# v002.net
KiCad netlist of a schematic drawn in EAGLE
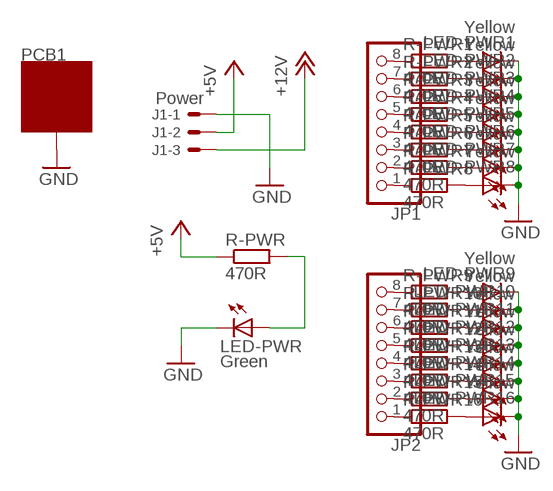
[diagram p0: schematic, sheet 1]

(export (version "E")
  (design (tool "Eeschema 10.0.6"))
  (components
    (comp (ref "J1")
      (value "Power")
      (footprint "eagle-import:6410-03")
      (libsource (lib "eagle-import") (part "22-?-0327-2031"))
    )
    (comp (ref "JP1")
      (value "PINHD-1X8")
      (footprint "eagle-import:1X08")
      (libsource (lib "eagle-import") (part "PINHD-1X8"))
    )
    (comp (ref "JP2")
      (value "PINHD-1X8")
      (footprint "eagle-import:1X08")
      (libsource (lib "eagle-import") (part "PINHD-1X8"))
    )
    (comp (ref "LED-PWR")
      (value "Green")
      (footprint "eagle-import:LED3MM")
      (libsource (lib "eagle-import") (part "LED3MM"))
    )
    (comp (ref "LED-PWR1")
      (value "Yellow")
      (footprint "eagle-import:LED3MM")
      (libsource (lib "eagle-import") (part "LED3MM"))
    )
    (comp (ref "LED-PWR2")
      (value "Yellow")
      (footprint "eagle-import:LED3MM")
      (libsource (lib "eagle-import") (part "LED3MM"))
    )
    (comp (ref "LED-PWR3")
      (value "Yellow")
      (footprint "eagle-import:LED3MM")
      (libsource (lib "eagle-import") (part "LED3MM"))
    )
    (comp (ref "LED-PWR4")
      (value "Yellow")
      (footprint "eagle-import:LED3MM")
      (libsource (lib "eagle-import") (part "LED3MM"))
    )
    (comp (ref "LED-PWR5")
      (value "Yellow")
      (footprint "eagle-import:LED3MM")
      (libsource (lib "eagle-import") (part "LED3MM"))
    )
    (comp (ref "LED-PWR6")
      (value "Yellow")
      (footprint "eagle-import:LED3MM")
      (libsource (lib "eagle-import") (part "LED3MM"))
    )
    (comp (ref "LED-PWR7")
      (value "Yellow")
      (footprint "eagle-import:LED3MM")
      (libsource (lib "eagle-import") (part "LED3MM"))
    )
    (comp (ref "LED-PWR8")
      (value "Yellow")
      (footprint "eagle-import:LED3MM")
      (libsource (lib "eagle-import") (part "LED3MM"))
    )
    (comp (ref "LED-PWR9")
      (value "Yellow")
      (footprint "eagle-import:LED3MM")
      (libsource (lib "eagle-import") (part "LED3MM"))
    )
    (comp (ref "LED-PWR10")
      (value "Yellow")
      (footprint "eagle-import:LED3MM")
      (libsource (lib "eagle-import") (part "LED3MM"))
    )
    (comp (ref "LED-PWR11")
      (value "Yellow")
      (footprint "eagle-import:LED3MM")
      (libsource (lib "eagle-import") (part "LED3MM"))
    )
    (comp (ref "LED-PWR12")
      (value "Yellow")
      (footprint "eagle-import:LED3MM")
      (libsource (lib "eagle-import") (part "LED3MM"))
    )
    (comp (ref "LED-PWR13")
      (value "Yellow")
      (footprint "eagle-import:LED3MM")
      (libsource (lib "eagle-import") (part "LED3MM"))
    )
    (comp (ref "LED-PWR14")
      (value "Yellow")
      (footprint "eagle-import:LED3MM")
      (libsource (lib "eagle-import") (part "LED3MM"))
    )
    (comp (ref "LED-PWR15")
      (value "Yellow")
      (footprint "eagle-import:LED3MM")
      (libsource (lib "eagle-import") (part "LED3MM"))
    )
    (comp (ref "LED-PWR16")
      (value "Yellow")
      (footprint "eagle-import:LED3MM")
      (libsource (lib "eagle-import") (part "LED3MM"))
    )
    (comp (ref "PCB1")
      (value "ZZZ_MODULE05X05")
      (footprint "eagle-import:ZZZ_MODULE_05X05")
      (libsource (lib "eagle-import") (part "ZZZ_MODULE05X05"))
    )
    (comp (ref "R-PWR")
      (value "470R")
      (footprint "eagle-import:0204_7")
      (libsource (lib "eagle-import") (part "R-EU_0204/7"))
    )
    (comp (ref "R-PWR1")
      (value "470R")
      (footprint "eagle-import:0204_7")
      (libsource (lib "eagle-import") (part "R-EU_0204/7"))
    )
    (comp (ref "R-PWR2")
      (value "470R")
      (footprint "eagle-import:0204_7")
      (libsource (lib "eagle-import") (part "R-EU_0204/7"))
    )
    (comp (ref "R-PWR3")
      (value "470R")
      (footprint "eagle-import:0204_7")
      (libsource (lib "eagle-import") (part "R-EU_0204/7"))
    )
    (comp (ref "R-PWR4")
      (value "470R")
      (footprint "eagle-import:0204_7")
      (libsource (lib "eagle-import") (part "R-EU_0204/7"))
    )
    (comp (ref "R-PWR5")
      (value "470R")
      (footprint "eagle-import:0204_7")
      (libsource (lib "eagle-import") (part "R-EU_0204/7"))
    )
    (comp (ref "R-PWR6")
      (value "470R")
      (footprint "eagle-import:0204_7")
      (libsource (lib "eagle-import") (part "R-EU_0204/7"))
    )
    (comp (ref "R-PWR7")
      (value "470R")
      (footprint "eagle-import:0204_7")
      (libsource (lib "eagle-import") (part "R-EU_0204/7"))
    )
    (comp (ref "R-PWR8")
      (value "470R")
      (footprint "eagle-import:0204_7")
      (libsource (lib "eagle-import") (part "R-EU_0204/7"))
    )
    (comp (ref "R-PWR9")
      (value "470R")
      (footprint "eagle-import:0204_7")
      (libsource (lib "eagle-import") (part "R-EU_0204/7"))
    )
    (comp (ref "R-PWR10")
      (value "470R")
      (footprint "eagle-import:0204_7")
      (libsource (lib "eagle-import") (part "R-EU_0204/7"))
    )
    (comp (ref "R-PWR11")
      (value "470R")
      (footprint "eagle-import:0204_7")
      (libsource (lib "eagle-import") (part "R-EU_0204/7"))
    )
    (comp (ref "R-PWR12")
      (value "470R")
      (footprint "eagle-import:0204_7")
      (libsource (lib "eagle-import") (part "R-EU_0204/7"))
    )
    (comp (ref "R-PWR13")
      (value "470R")
      (footprint "eagle-import:0204_7")
      (libsource (lib "eagle-import") (part "R-EU_0204/7"))
    )
    (comp (ref "R-PWR14")
      (value "470R")
      (footprint "eagle-import:0204_7")
      (libsource (lib "eagle-import") (part "R-EU_0204/7"))
    )
    (comp (ref "R-PWR15")
      (value "470R")
      (footprint "eagle-import:0204_7")
      (libsource (lib "eagle-import") (part "R-EU_0204/7"))
    )
    (comp (ref "R-PWR16")
      (value "470R")
      (footprint "eagle-import:0204_7")
      (libsource (lib "eagle-import") (part "R-EU_0204/7"))
    )
  )
  (nets
    (net (code "1") (name "+5V") (class "Default")
      (node (ref "J1") (pin "2") (pinfunction "S_2") (pintype "passive"))
      (node (ref "R-PWR") (pin "1") (pinfunction "1_1") (pintype "passive"))
    )
    (net (code "2") (name "+12V") (class "Default")
      (node (ref "J1") (pin "3") (pinfunction "S_3") (pintype "passive"))
    )
    (net (code "3") (name "GND") (class "Default")
      (node (ref "J1") (pin "1") (pinfunction "S_1") (pintype "passive"))
      (node (ref "LED-PWR") (pin "K") (pinfunction "C_K") (pintype "passive"))
      (node (ref "LED-PWR1") (pin "K") (pinfunction "C_K") (pintype "passive"))
      (node (ref "LED-PWR10") (pin "K") (pinfunction "C_K") (pintype "passive"))
      (node (ref "LED-PWR11") (pin "K") (pinfunction "C_K") (pintype "passive"))
      (node (ref "LED-PWR12") (pin "K") (pinfunction "C_K") (pintype "passive"))
      (node (ref "LED-PWR13") (pin "K") (pinfunction "C_K") (pintype "passive"))
      (node (ref "LED-PWR14") (pin "K") (pinfunction "C_K") (pintype "passive"))
      (node (ref "LED-PWR15") (pin "K") (pinfunction "C_K") (pintype "passive"))
      (node (ref "LED-PWR16") (pin "K") (pinfunction "C_K") (pintype "passive"))
      (node (ref "LED-PWR2") (pin "K") (pinfunction "C_K") (pintype "passive"))
      (node (ref "LED-PWR3") (pin "K") (pinfunction "C_K") (pintype "passive"))
      (node (ref "LED-PWR4") (pin "K") (pinfunction "C_K") (pintype "passive"))
      (node (ref "LED-PWR5") (pin "K") (pinfunction "C_K") (pintype "passive"))
      (node (ref "LED-PWR6") (pin "K") (pinfunction "C_K") (pintype "passive"))
      (node (ref "LED-PWR7") (pin "K") (pinfunction "C_K") (pintype "passive"))
      (node (ref "LED-PWR8") (pin "K") (pinfunction "C_K") (pintype "passive"))
      (node (ref "LED-PWR9") (pin "K") (pinfunction "C_K") (pintype "passive"))
      (node (ref "PCB1") (pin "GND@1") (pinfunction "GND_GND@1") (pintype "power_in"))
      (node (ref "PCB1") (pin "GND@2") (pinfunction "GND_GND@2") (pintype "power_in"))
      (node (ref "PCB1") (pin "GND@3") (pinfunction "GND_GND@3") (pintype "power_in"))
      (node (ref "PCB1") (pin "GND@4") (pinfunction "GND_GND@4") (pintype "power_in"))
      (node (ref "PCB1") (pin "GND@5") (pinfunction "GND_GND@5") (pintype "power_in"))
      (node (ref "PCB1") (pin "GND@6") (pinfunction "GND_GND@6") (pintype "power_in"))
      (node (ref "PCB1") (pin "GND@7") (pinfunction "GND_GND@7") (pintype "power_in"))
      (node (ref "PCB1") (pin "GND@8") (pinfunction "GND_GND@8") (pintype "power_in"))
    )
    (net (code "4") (name "Net-(JP1-Pad1)") (class "Default")
      (node (ref "JP1") (pin "1") (pinfunction "1_1") (pintype "passive"))
      (node (ref "R-PWR8") (pin "1") (pinfunction "1_1") (pintype "passive"))
    )
    (net (code "5") (name "Net-(JP1-Pad2)") (class "Default")
      (node (ref "JP1") (pin "2") (pinfunction "2_2") (pintype "passive"))
      (node (ref "R-PWR7") (pin "1") (pinfunction "1_1") (pintype "passive"))
    )
    (net (code "6") (name "Net-(JP1-Pad3)") (class "Default")
      (node (ref "JP1") (pin "3") (pinfunction "3_3") (pintype "passive"))
      (node (ref "R-PWR6") (pin "1") (pinfunction "1_1") (pintype "passive"))
    )
    (net (code "7") (name "Net-(JP1-Pad4)") (class "Default")
      (node (ref "JP1") (pin "4") (pinfunction "4_4") (pintype "passive"))
      (node (ref "R-PWR5") (pin "1") (pinfunction "1_1") (pintype "passive"))
    )
    (net (code "8") (name "Net-(JP1-Pad5)") (class "Default")
      (node (ref "JP1") (pin "5") (pinfunction "5_5") (pintype "passive"))
      (node (ref "R-PWR4") (pin "1") (pinfunction "1_1") (pintype "passive"))
    )
    (net (code "9") (name "Net-(JP1-Pad6)") (class "Default")
      (node (ref "JP1") (pin "6") (pinfunction "6_6") (pintype "passive"))
      (node (ref "R-PWR3") (pin "1") (pinfunction "1_1") (pintype "passive"))
    )
    (net (code "10") (name "Net-(JP1-Pad7)") (class "Default")
      (node (ref "JP1") (pin "7") (pinfunction "7_7") (pintype "passive"))
      (node (ref "R-PWR2") (pin "1") (pinfunction "1_1") (pintype "passive"))
    )
    (net (code "11") (name "Net-(JP1-Pad8)") (class "Default")
      (node (ref "JP1") (pin "8") (pinfunction "8_8") (pintype "passive"))
      (node (ref "R-PWR1") (pin "1") (pinfunction "1_1") (pintype "passive"))
    )
    (net (code "12") (name "Net-(JP2-Pad1)") (class "Default")
      (node (ref "JP2") (pin "1") (pinfunction "1_1") (pintype "passive"))
      (node (ref "R-PWR16") (pin "1") (pinfunction "1_1") (pintype "passive"))
    )
    (net (code "13") (name "Net-(JP2-Pad2)") (class "Default")
      (node (ref "JP2") (pin "2") (pinfunction "2_2") (pintype "passive"))
      (node (ref "R-PWR15") (pin "1") (pinfunction "1_1") (pintype "passive"))
    )
    (net (code "14") (name "Net-(JP2-Pad3)") (class "Default")
      (node (ref "JP2") (pin "3") (pinfunction "3_3") (pintype "passive"))
      (node (ref "R-PWR14") (pin "1") (pinfunction "1_1") (pintype "passive"))
    )
    (net (code "15") (name "Net-(JP2-Pad4)") (class "Default")
      (node (ref "JP2") (pin "4") (pinfunction "4_4") (pintype "passive"))
      (node (ref "R-PWR13") (pin "1") (pinfunction "1_1") (pintype "passive"))
    )
    (net (code "16") (name "Net-(JP2-Pad5)") (class "Default")
      (node (ref "JP2") (pin "5") (pinfunction "5_5") (pintype "passive"))
      (node (ref "R-PWR12") (pin "1") (pinfunction "1_1") (pintype "passive"))
    )
    (net (code "17") (name "Net-(JP2-Pad6)") (class "Default")
      (node (ref "JP2") (pin "6") (pinfunction "6_6") (pintype "passive"))
      (node (ref "R-PWR11") (pin "1") (pinfunction "1_1") (pintype "passive"))
    )
    (net (code "18") (name "Net-(JP2-Pad7)") (class "Default")
      (node (ref "JP2") (pin "7") (pinfunction "7_7") (pintype "passive"))
      (node (ref "R-PWR10") (pin "1") (pinfunction "1_1") (pintype "passive"))
    )
    (net (code "19") (name "Net-(JP2-Pad8)") (class "Default")
      (node (ref "JP2") (pin "8") (pinfunction "8_8") (pintype "passive"))
      (node (ref "R-PWR9") (pin "1") (pinfunction "1_1") (pintype "passive"))
    )
    (net (code "20") (name "Net-(LED-PWR-PadA)") (class "Default")
      (node (ref "LED-PWR") (pin "A") (pinfunction "A_A") (pintype "passive"))
      (node (ref "R-PWR") (pin "2") (pinfunction "2_2") (pintype "passive"))
    )
    (net (code "21") (name "Net-(LED-PWR1-PadA)") (class "Default")
      (node (ref "LED-PWR1") (pin "A") (pinfunction "A_A") (pintype "passive"))
      (node (ref "R-PWR1") (pin "2") (pinfunction "2_2") (pintype "passive"))
    )
    (net (code "22") (name "Net-(LED-PWR2-PadA)") (class "Default")
      (node (ref "LED-PWR2") (pin "A") (pinfunction "A_A") (pintype "passive"))
      (node (ref "R-PWR2") (pin "2") (pinfunction "2_2") (pintype "passive"))
    )
    (net (code "23") (name "Net-(LED-PWR3-PadA)") (class "Default")
      (node (ref "LED-PWR3") (pin "A") (pinfunction "A_A") (pintype "passive"))
      (node (ref "R-PWR3") (pin "2") (pinfunction "2_2") (pintype "passive"))
    )
    (net (code "24") (name "Net-(LED-PWR4-PadA)") (class "Default")
      (node (ref "LED-PWR4") (pin "A") (pinfunction "A_A") (pintype "passive"))
      (node (ref "R-PWR4") (pin "2") (pinfunction "2_2") (pintype "passive"))
    )
    (net (code "25") (name "Net-(LED-PWR5-PadA)") (class "Default")
      (node (ref "LED-PWR5") (pin "A") (pinfunction "A_A") (pintype "passive"))
      (node (ref "R-PWR5") (pin "2") (pinfunction "2_2") (pintype "passive"))
    )
    (net (code "26") (name "Net-(LED-PWR6-PadA)") (class "Default")
      (node (ref "LED-PWR6") (pin "A") (pinfunction "A_A") (pintype "passive"))
      (node (ref "R-PWR6") (pin "2") (pinfunction "2_2") (pintype "passive"))
    )
    (net (code "27") (name "Net-(LED-PWR7-PadA)") (class "Default")
      (node (ref "LED-PWR7") (pin "A") (pinfunction "A_A") (pintype "passive"))
      (node (ref "R-PWR7") (pin "2") (pinfunction "2_2") (pintype "passive"))
    )
    (net (code "28") (name "Net-(LED-PWR8-PadA)") (class "Default")
      (node (ref "LED-PWR8") (pin "A") (pinfunction "A_A") (pintype "passive"))
      (node (ref "R-PWR8") (pin "2") (pinfunction "2_2") (pintype "passive"))
    )
    (net (code "29") (name "Net-(LED-PWR9-PadA)") (class "Default")
      (node (ref "LED-PWR9") (pin "A") (pinfunction "A_A") (pintype "passive"))
      (node (ref "R-PWR9") (pin "2") (pinfunction "2_2") (pintype "passive"))
    )
    (net (code "30") (name "Net-(LED-PWR10-PadA)") (class "Default")
      (node (ref "LED-PWR10") (pin "A") (pinfunction "A_A") (pintype "passive"))
      (node (ref "R-PWR10") (pin "2") (pinfunction "2_2") (pintype "passive"))
    )
    (net (code "31") (name "Net-(LED-PWR11-PadA)") (class "Default")
      (node (ref "LED-PWR11") (pin "A") (pinfunction "A_A") (pintype "passive"))
      (node (ref "R-PWR11") (pin "2") (pinfunction "2_2") (pintype "passive"))
    )
    (net (code "32") (name "Net-(LED-PWR12-PadA)") (class "Default")
      (node (ref "LED-PWR12") (pin "A") (pinfunction "A_A") (pintype "passive"))
      (node (ref "R-PWR12") (pin "2") (pinfunction "2_2") (pintype "passive"))
    )
    (net (code "33") (name "Net-(LED-PWR13-PadA)") (class "Default")
      (node (ref "LED-PWR13") (pin "A") (pinfunction "A_A") (pintype "passive"))
      (node (ref "R-PWR13") (pin "2") (pinfunction "2_2") (pintype "passive"))
    )
    (net (code "34") (name "Net-(LED-PWR14-PadA)") (class "Default")
      (node (ref "LED-PWR14") (pin "A") (pinfunction "A_A") (pintype "passive"))
      (node (ref "R-PWR14") (pin "2") (pinfunction "2_2") (pintype "passive"))
    )
    (net (code "35") (name "Net-(LED-PWR15-PadA)") (class "Default")
      (node (ref "LED-PWR15") (pin "A") (pinfunction "A_A") (pintype "passive"))
      (node (ref "R-PWR15") (pin "2") (pinfunction "2_2") (pintype "passive"))
    )
    (net (code "36") (name "Net-(LED-PWR16-PadA)") (class "Default")
      (node (ref "LED-PWR16") (pin "A") (pinfunction "A_A") (pintype "passive"))
      (node (ref "R-PWR16") (pin "2") (pinfunction "2_2") (pintype "passive"))
    )
  )
)
